# HelloWorldEAther.net
KiCad netlist of a schematic drawn in EAGLE
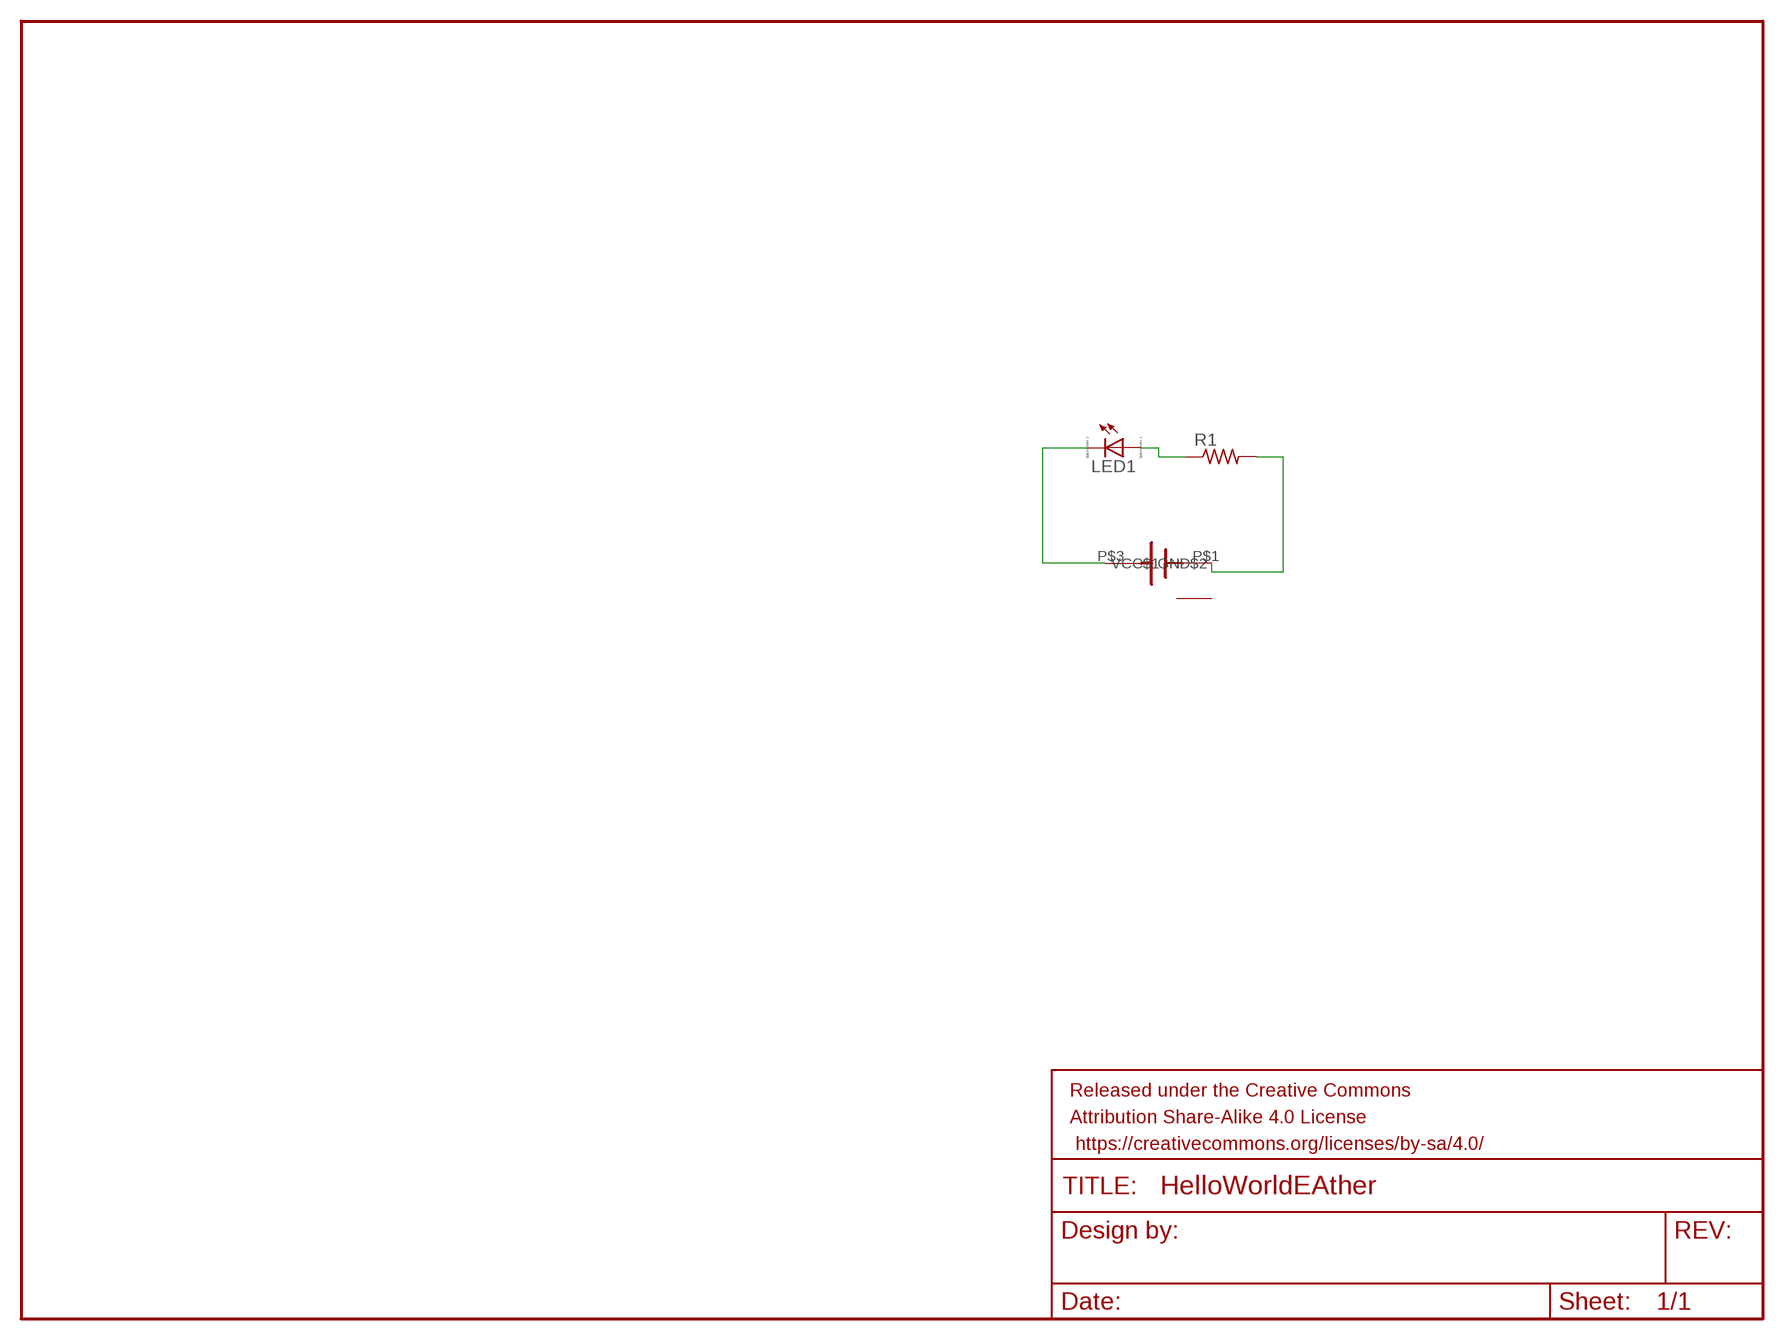
[diagram p0: schematic, sheet 1]

(export (version "E")
  (design (tool "Eeschema 10.0.6"))
  (components
    (comp (ref "FRAME1")
      (value "FRAME-LETTER")
      (footprint "eagle-import:CREATIVE_COMMONS")
      (libsource (lib "eagle-import") (part "FRAME-LETTER"))
    )
    (comp (ref "LED1")
      (value "LED_E")
      (footprint "eagle-import:LED_1206")
      (libsource (lib "eagle-import") (part "LED_E"))
    )
    (comp (ref "R1")
      (value "R-US_R0805")
      (footprint "eagle-import:R0805")
      (libsource (lib "eagle-import") (part "R-US_R0805"))
    )
    (comp (ref "U$1")
      (value "CR1025")
      (footprint "eagle-import:CR1025")
      (libsource (lib "eagle-import") (part "CR1025"))
    )
  )
  (nets
    (net (code "1") (name "/VCC") (class "Default")
      (node (ref "U$1") (pin "P$2") (pinfunction "VCC_P$2") (pintype "power_in"))
    )
    (net (code "2") (name "Net-(LED1-PadA)") (class "Default")
      (node (ref "LED1") (pin "A") (pinfunction "A_A") (pintype "passive"))
      (node (ref "R1") (pin "1") (pinfunction "1_1") (pintype "passive"))
    )
    (net (code "3") (name "Net-(U$1-GND$2)") (class "Default")
      (node (ref "LED1") (pin "C") (pinfunction "C_C") (pintype "passive"))
      (node (ref "U$1") (pin "P$3") (pinfunction "GND$2_P$3") (pintype "power_in"))
    )
    (net (code "4") (name "Net-(U$1-VCC$1)") (class "Default")
      (node (ref "R1") (pin "2") (pinfunction "2_2") (pintype "passive"))
      (node (ref "U$1") (pin "P$1") (pinfunction "VCC$1_P$1") (pintype "power_in"))
    )
  )
)
